# Audio.net
KiCad netlist of a schematic drawn in Altium Designer
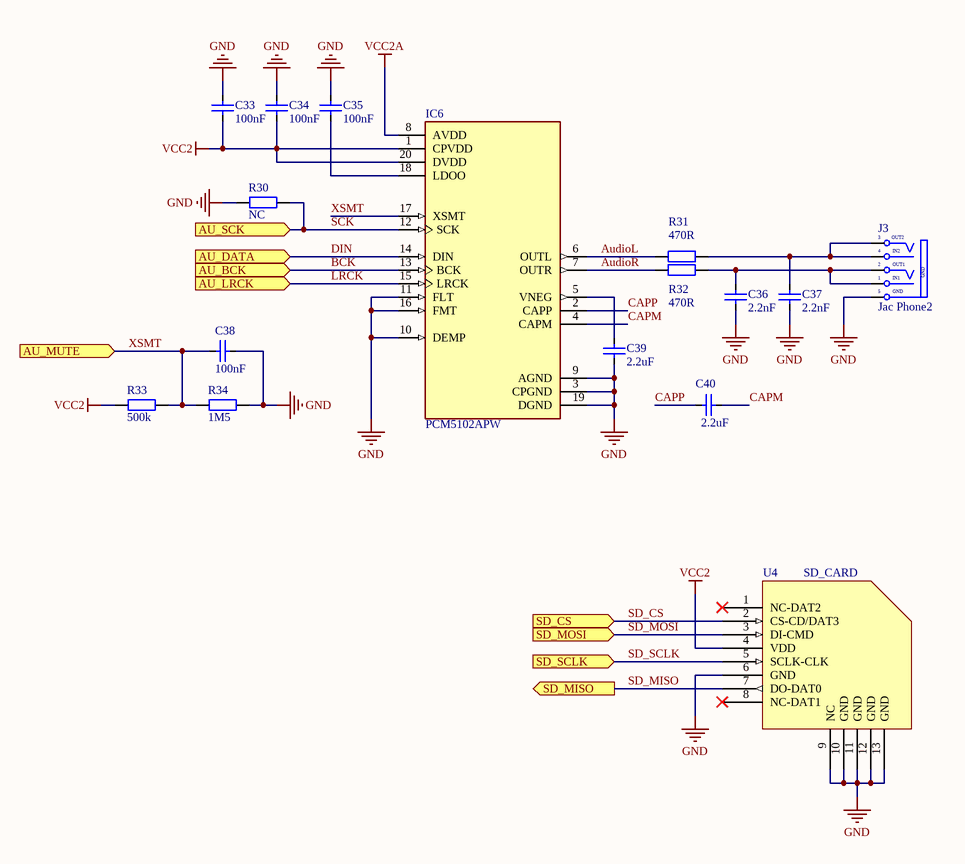
[diagram p0: Audio.SchDoc]

(export (version "E")
  (design (tool "Eeschema 10.0.6"))
  (components
    (comp (ref "C33")
      (value "100nF")
      (footprint "CAP_0603")
      (description "Capacitor")
      (fields (field (name "PUBLISHER") "Altium Limited"))
      (libsource (lib "My Library") (part "CapSMD"))
    )
    (comp (ref "C34")
      (value "100nF")
      (footprint "CAP_0603")
      (description "Capacitor")
      (fields (field (name "PUBLISHER") "Altium Limited"))
      (libsource (lib "My Library") (part "CapSMD"))
    )
    (comp (ref "C35")
      (value "100nF")
      (footprint "CAP_0603")
      (description "Capacitor")
      (fields (field (name "PUBLISHER") "Altium Limited"))
      (libsource (lib "My Library") (part "CapSMD"))
    )
    (comp (ref "C36")
      (value "2.2nF")
      (footprint "CAP_0603")
      (description "Capacitor")
      (fields (field (name "PUBLISHER") "Altium Limited"))
      (libsource (lib "My Library") (part "CapSMD"))
    )
    (comp (ref "C37")
      (value "2.2nF")
      (footprint "CAP_0603")
      (description "Capacitor")
      (fields (field (name "PUBLISHER") "Altium Limited"))
      (libsource (lib "My Library") (part "CapSMD"))
    )
    (comp (ref "C38")
      (value "100nF")
      (footprint "CAP_0603")
      (description "Capacitor")
      (fields (field (name "PUBLISHER") "Altium Limited"))
      (libsource (lib "My Library") (part "CapSMD"))
    )
    (comp (ref "C39")
      (value "2.2uF")
      (footprint "CAP_0603")
      (description "Capacitor")
      (fields (field (name "PUBLISHER") "Altium Limited"))
      (libsource (lib "My Library") (part "CapSMD"))
    )
    (comp (ref "C40")
      (value "2.2uF")
      (footprint "CAP_0603")
      (description "Capacitor")
      (fields (field (name "PUBLISHER") "Altium Limited"))
      (libsource (lib "My Library") (part "CapSMD"))
    )
    (comp (ref "IC6")
      (value "PCM5102APW")
      (footprint "TSSOP-20")
      (description "Audio decode")
      (libsource (lib "My Library") (part "PCM5102APW"))
    )
    (comp (ref "J3")
      (value "Jac Phone2")
      (footprint "JacPhone2")
      (description "Jac Phone Stereo")
      (fields (field (name "CREAT BY") "VanDungEvn@Gmail.com"))
      (libsource (lib "My Library") (part "Jac Phone2"))
    )
    (comp (ref "R30")
      (value "NC")
      (footprint "RES-SMD-0603")
      (description "Resistor SMD")
      (fields
        (field (name "MANUFACTURER") "Generic Components")
        (field (name "PUBLISHER") "Altium Hobart Technology Centre")
      )
      (libsource (lib "My Library") (part "Resistor - SMD"))
    )
    (comp (ref "R31")
      (value "470R")
      (footprint "RES-SMD-0603")
      (description "Resistor SMD")
      (fields
        (field (name "MANUFACTURER") "Generic Components")
        (field (name "PUBLISHER") "Altium Hobart Technology Centre")
      )
      (libsource (lib "My Library") (part "Resistor - SMD"))
    )
    (comp (ref "R32")
      (value "470R")
      (footprint "RES-SMD-0603")
      (description "Resistor SMD")
      (fields
        (field (name "MANUFACTURER") "Generic Components")
        (field (name "PUBLISHER") "Altium Hobart Technology Centre")
      )
      (libsource (lib "My Library") (part "Resistor - SMD"))
    )
    (comp (ref "R33")
      (value "500k")
      (footprint "RES-SMD-0603")
      (description "Resistor SMD")
      (fields
        (field (name "MANUFACTURER") "Generic Components")
        (field (name "PUBLISHER") "Altium Hobart Technology Centre")
      )
      (libsource (lib "My Library") (part "Resistor - SMD"))
    )
    (comp (ref "R34")
      (value "1M5")
      (footprint "RES-SMD-0603")
      (description "Resistor SMD")
      (fields
        (field (name "MANUFACTURER") "Generic Components")
        (field (name "PUBLISHER") "Altium Hobart Technology Centre")
      )
      (libsource (lib "My Library") (part "Resistor - SMD"))
    )
    (comp (ref "U4")
      (value "SD_CARD")
      (footprint "MICROSD2")
      (description "SD/MMC holder")
      (libsource (lib "My Library") (part "MicroSD"))
    )
  )
  (nets
    (net (code "1") (name "/AudioL") (class "Default")
      (node (ref "IC6") (pin "6") (pinfunction "OUTL_6") (pintype "output"))
      (node (ref "R31") (pin "2") (pinfunction "2_2") (pintype "passive"))
    )
    (net (code "2") (name "/AudioR") (class "Default")
      (node (ref "IC6") (pin "7") (pinfunction "OUTR_7") (pintype "output"))
      (node (ref "R32") (pin "2") (pinfunction "2_2") (pintype "passive"))
    )
    (net (code "3") (name "/BCK") (class "Default")
      (node (ref "IC6") (pin "13") (pinfunction "BCK_13") (pintype "input"))
    )
    (net (code "4") (name "/CAPM") (class "Default")
      (node (ref "C40") (pin "2") (pinfunction "2_2") (pintype "passive"))
      (node (ref "IC6") (pin "4") (pinfunction "CAPM_4") (pintype "passive"))
    )
    (net (code "5") (name "/CAPP") (class "Default")
      (node (ref "C40") (pin "1") (pinfunction "1_1") (pintype "passive"))
      (node (ref "IC6") (pin "2") (pinfunction "CAPP_2") (pintype "passive"))
    )
    (net (code "6") (name "/DIN") (class "Default")
      (node (ref "IC6") (pin "14") (pinfunction "DIN_14") (pintype "input"))
    )
    (net (code "7") (name "/LRCK") (class "Default")
      (node (ref "IC6") (pin "15") (pinfunction "LRCK_15") (pintype "input"))
    )
    (net (code "8") (name "/SCK") (class "Default")
      (node (ref "IC6") (pin "12") (pinfunction "SCK_12") (pintype "input"))
      (node (ref "R30") (pin "2") (pinfunction "2_2") (pintype "passive"))
    )
    (net (code "9") (name "/SD_CS") (class "Default")
      (node (ref "U4") (pin "2") (pinfunction "CS-CD/DAT3_2") (pintype "input"))
    )
    (net (code "10") (name "/SD_MISO") (class "Default")
      (node (ref "U4") (pin "7") (pinfunction "DO-DAT0_7") (pintype "output"))
    )
    (net (code "11") (name "/SD_MOSI") (class "Default")
      (node (ref "U4") (pin "3") (pinfunction "DI-CMD_3") (pintype "input"))
    )
    (net (code "12") (name "/SD_SCLK") (class "Default")
      (node (ref "U4") (pin "5") (pinfunction "SCLK-CLK_5") (pintype "input"))
    )
    (net (code "13") (name "/XSMT") (class "Default")
      (node (ref "C38") (pin "1") (pinfunction "1_1") (pintype "passive"))
      (node (ref "IC6") (pin "17") (pinfunction "XSMT_17") (pintype "input"))
      (node (ref "R33") (pin "2") (pinfunction "2_2") (pintype "passive"))
      (node (ref "R34") (pin "1") (pinfunction "1_1") (pintype "passive"))
    )
    (net (code "14") (name "GND") (class "Default")
      (node (ref "C33") (pin "1") (pinfunction "1_1") (pintype "passive"))
      (node (ref "C34") (pin "1") (pinfunction "1_1") (pintype "passive"))
      (node (ref "C35") (pin "1") (pinfunction "1_1") (pintype "passive"))
      (node (ref "C36") (pin "1") (pinfunction "1_1") (pintype "passive"))
      (node (ref "C37") (pin "1") (pinfunction "1_1") (pintype "passive"))
      (node (ref "C38") (pin "2") (pinfunction "2_2") (pintype "passive"))
      (node (ref "C39") (pin "1") (pinfunction "1_1") (pintype "passive"))
      (node (ref "IC6") (pin "10") (pinfunction "DEMP_10") (pintype "input"))
      (node (ref "IC6") (pin "11") (pinfunction "FLT_11") (pintype "input"))
      (node (ref "IC6") (pin "16") (pinfunction "FMT_16") (pintype "input"))
      (node (ref "IC6") (pin "19") (pinfunction "DGND_19") (pintype "power_in"))
      (node (ref "IC6") (pin "3") (pinfunction "CPGND_3") (pintype "power_in"))
      (node (ref "IC6") (pin "9") (pinfunction "AGND_9") (pintype "power_in"))
      (node (ref "J3") (pin "5") (pinfunction "GND_5") (pintype "passive"))
      (node (ref "R30") (pin "1") (pinfunction "1_1") (pintype "passive"))
      (node (ref "R34") (pin "2") (pinfunction "2_2") (pintype "passive"))
      (node (ref "U4") (pin "10") (pinfunction "GND_10") (pintype "passive"))
      (node (ref "U4") (pin "11") (pinfunction "GND_11") (pintype "passive"))
      (node (ref "U4") (pin "12") (pinfunction "GND_12") (pintype "passive"))
      (node (ref "U4") (pin "13") (pinfunction "GND_13") (pintype "passive"))
      (node (ref "U4") (pin "6") (pinfunction "GND_6") (pintype "passive"))
      (node (ref "U4") (pin "9") (pinfunction "NC_9") (pintype "passive"))
    )
    (net (code "15") (name "Net-(C36-Pad2)") (class "Default")
      (node (ref "C36") (pin "2") (pinfunction "2_2") (pintype "passive"))
      (node (ref "J3") (pin "1") (pinfunction "S1_1") (pintype "power_in"))
      (node (ref "J3") (pin "2") (pinfunction "S1_2") (pintype "passive"))
      (node (ref "R32") (pin "1") (pinfunction "1_1") (pintype "passive"))
    )
    (net (code "16") (name "Net-(IC6-LDOO)") (class "Default")
      (node (ref "C35") (pin "2") (pinfunction "2_2") (pintype "passive"))
      (node (ref "IC6") (pin "18") (pinfunction "LDOO_18") (pintype "power_in"))
    )
    (net (code "17") (name "Net-(IC6-VNEG)") (class "Default")
      (node (ref "C39") (pin "2") (pinfunction "2_2") (pintype "passive"))
      (node (ref "IC6") (pin "5") (pinfunction "VNEG_5") (pintype "output"))
    )
    (net (code "18") (name "Net-(J3-S)") (class "Default")
      (node (ref "C37") (pin "2") (pinfunction "2_2") (pintype "passive"))
      (node (ref "J3") (pin "3") (pinfunction "TN_3") (pintype "passive"))
      (node (ref "J3") (pin "4") (pinfunction "S_4") (pintype "power_in"))
      (node (ref "R31") (pin "1") (pinfunction "1_1") (pintype "passive"))
    )
    (net (code "19") (name "VCC2") (class "Default")
      (node (ref "C33") (pin "2") (pinfunction "2_2") (pintype "passive"))
      (node (ref "C34") (pin "2") (pinfunction "2_2") (pintype "passive"))
      (node (ref "IC6") (pin "1") (pinfunction "CPVDD_1") (pintype "power_in"))
      (node (ref "IC6") (pin "20") (pinfunction "DVDD_20") (pintype "power_in"))
      (node (ref "R33") (pin "1") (pinfunction "1_1") (pintype "passive"))
      (node (ref "U4") (pin "4") (pinfunction "VDD_4") (pintype "passive"))
    )
    (net (code "20") (name "VCC2A") (class "Default")
      (node (ref "IC6") (pin "8") (pinfunction "AVDD_8") (pintype "power_in"))
    )
    (net (code "21") (name "unconnected-(U4-NC-DAT1-Pad8)") (class "Default")
      (node (ref "U4") (pin "8") (pinfunction "NC-DAT1_8") (pintype "passive+no_connect"))
    )
    (net (code "22") (name "unconnected-(U4-NC-DAT2-Pad1)") (class "Default")
      (node (ref "U4") (pin "1") (pinfunction "NC-DAT2_1") (pintype "passive+no_connect"))
    )
  )
)
